# tracker.net
KiCad netlist of a schematic drawn in EAGLE
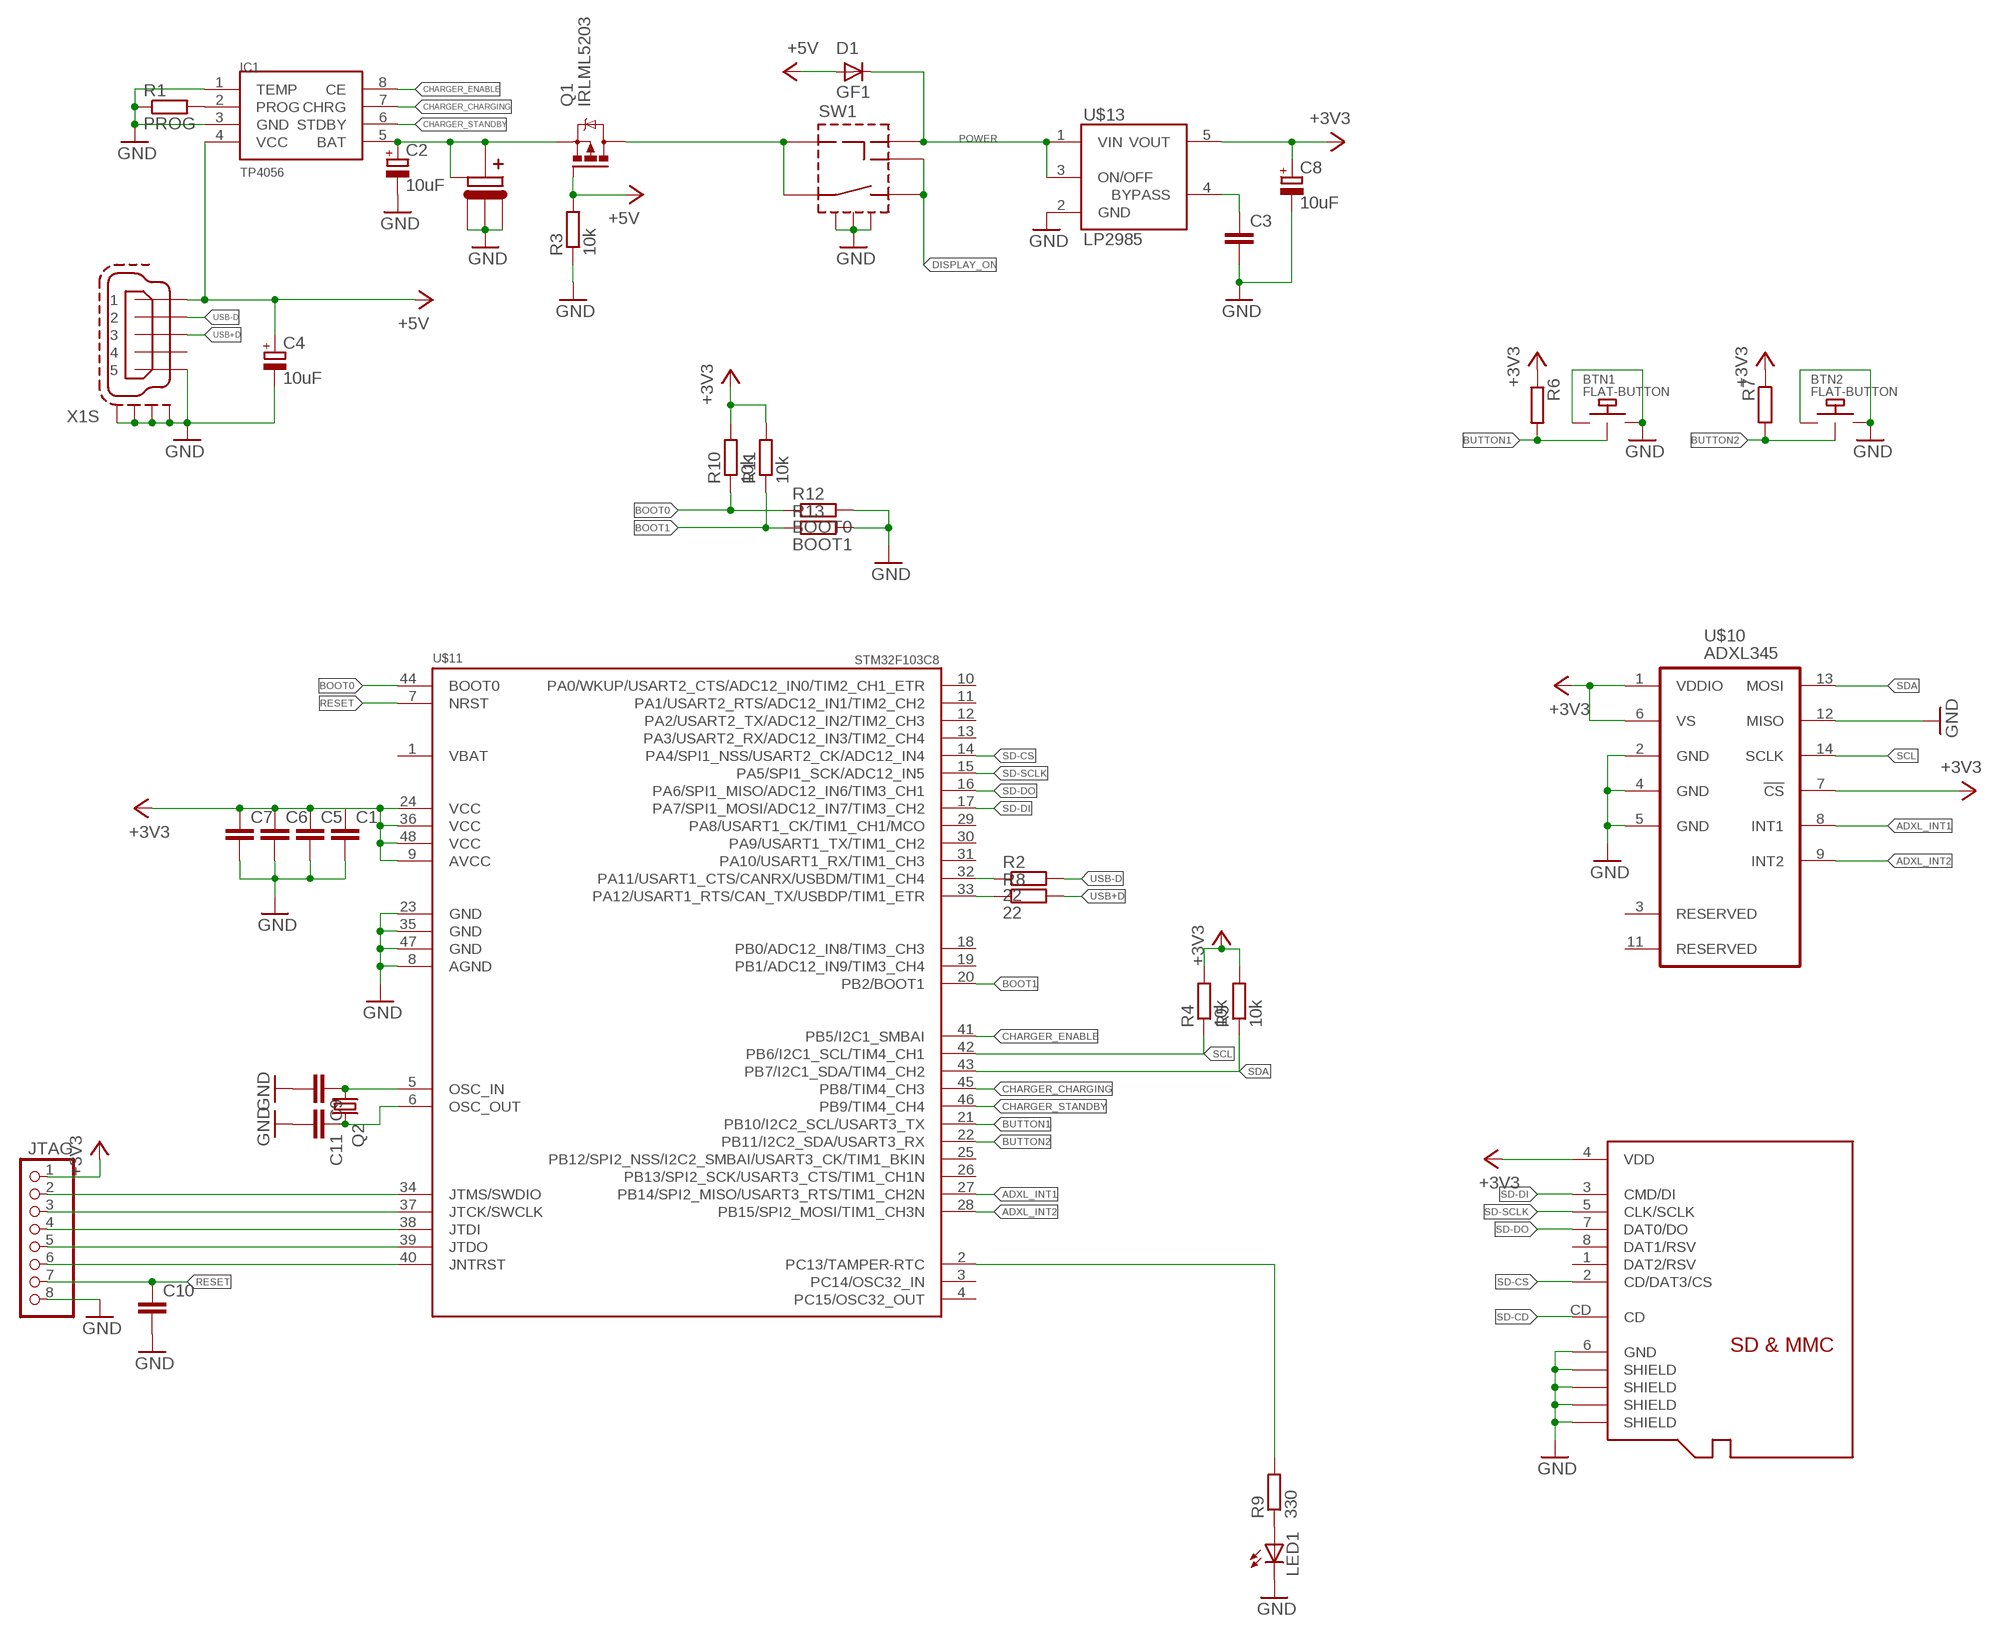
[diagram p0: schematic, sheet 1]

(export (version "E")
  (design (tool "Eeschema 10.0.6"))
  (components
    (comp (ref "BTN1")
      (value "FLAT-BUTTON")
      (footprint "eagle-import:FLAT-BUTTON")
      (libsource (lib "eagle-import") (part "FLAT-BUTTON"))
    )
    (comp (ref "BTN2")
      (value "FLAT-BUTTON")
      (footprint "eagle-import:FLAT-BUTTON")
      (libsource (lib "eagle-import") (part "FLAT-BUTTON"))
    )
    (comp (ref "C1")
      (value "C-EUC0805K")
      (footprint "eagle-import:C0805K")
      (libsource (lib "eagle-import") (part "C-EUC0805K"))
    )
    (comp (ref "C2")
      (value "10uF")
      (footprint "eagle-import:B_3528-21W")
      (libsource (lib "eagle-import") (part "CPOL-EUB/3528-21W"))
    )
    (comp (ref "C3")
      (value "C-EUC0805K")
      (footprint "eagle-import:C0805K")
      (libsource (lib "eagle-import") (part "C-EUC0805K"))
    )
    (comp (ref "C4")
      (value "10uF")
      (footprint "eagle-import:B_3528-21W")
      (libsource (lib "eagle-import") (part "CPOL-EUB/3528-21W"))
    )
    (comp (ref "C5")
      (value "C-EUC0805K")
      (footprint "eagle-import:C0805K")
      (libsource (lib "eagle-import") (part "C-EUC0805K"))
    )
    (comp (ref "C6")
      (value "C-EUC0805K")
      (footprint "eagle-import:C0805K")
      (libsource (lib "eagle-import") (part "C-EUC0805K"))
    )
    (comp (ref "C7")
      (value "C-EUC0805K")
      (footprint "eagle-import:C0805K")
      (libsource (lib "eagle-import") (part "C-EUC0805K"))
    )
    (comp (ref "C8")
      (value "10uF")
      (footprint "eagle-import:B_3528-21W")
      (libsource (lib "eagle-import") (part "CPOL-EUB/3528-21W"))
    )
    (comp (ref "C9")
      (value "C-EUC0805K")
      (footprint "eagle-import:C0805K")
      (libsource (lib "eagle-import") (part "C-EUC0805K"))
    )
    (comp (ref "C10")
      (value "C-EUC0805K")
      (footprint "eagle-import:C0805K")
      (libsource (lib "eagle-import") (part "C-EUC0805K"))
    )
    (comp (ref "C11")
      (value "C-EUC0805K")
      (footprint "eagle-import:C0805K")
      (libsource (lib "eagle-import") (part "C-EUC0805K"))
    )
    (comp (ref "D1")
      (value "GF1")
      (footprint "eagle-import:SMA-DO214AC")
      (libsource (lib "eagle-import") (part "GF1"))
    )
    (comp (ref "IC1")
      (value "TP4056")
      (footprint "eagle-import:SOP-8")
      (libsource (lib "eagle-import") (part "TP4056"))
    )
    (comp (ref "JTAG")
      (value "PINHD-1X8")
      (footprint "eagle-import:PLL1.27-1X8")
      (libsource (lib "eagle-import") (part "PINHD-1X8"))
    )
    (comp (ref "LED1")
      (value "LEDSML1206")
      (footprint "eagle-import:SML1206")
      (libsource (lib "eagle-import") (part "LEDSML1206"))
    )
    (comp (ref "Q1")
      (value "IRLML5203")
      (footprint "eagle-import:MICRO3")
      (libsource (lib "eagle-import") (part "IRLML5203"))
    )
    (comp (ref "Q2")
      (value "CRYSTALHC49S")
      (footprint "eagle-import:HC49_S")
      (libsource (lib "eagle-import") (part "CRYSTALHC49S"))
    )
    (comp (ref "R1")
      (value "PROG")
      (footprint "eagle-import:M0805")
      (libsource (lib "eagle-import") (part "R-EU_M0805"))
    )
    (comp (ref "R2")
      (value "22")
      (footprint "eagle-import:R0805")
      (libsource (lib "eagle-import") (part "R-EU_R0805"))
    )
    (comp (ref "R3")
      (value "10k")
      (footprint "eagle-import:R0805")
      (libsource (lib "eagle-import") (part "R-EU_R0805"))
    )
    (comp (ref "R4")
      (value "10k")
      (footprint "eagle-import:R0805")
      (libsource (lib "eagle-import") (part "R-EU_R0805"))
    )
    (comp (ref "R5")
      (value "10k")
      (footprint "eagle-import:R0805")
      (libsource (lib "eagle-import") (part "R-EU_R0805"))
    )
    (comp (ref "R6")
      (value "R-EU_R0805")
      (footprint "eagle-import:R0805")
      (libsource (lib "eagle-import") (part "R-EU_R0805"))
    )
    (comp (ref "R7")
      (value "R-EU_R0805")
      (footprint "eagle-import:R0805")
      (libsource (lib "eagle-import") (part "R-EU_R0805"))
    )
    (comp (ref "R8")
      (value "22")
      (footprint "eagle-import:R0805")
      (libsource (lib "eagle-import") (part "R-EU_R0805"))
    )
    (comp (ref "R9")
      (value "330")
      (footprint "eagle-import:R0805")
      (libsource (lib "eagle-import") (part "R-EU_R0805"))
    )
    (comp (ref "R10")
      (value "10k")
      (footprint "eagle-import:R0805")
      (libsource (lib "eagle-import") (part "R-EU_R0805"))
    )
    (comp (ref "R11")
      (value "10k")
      (footprint "eagle-import:R0805")
      (libsource (lib "eagle-import") (part "R-EU_R0805"))
    )
    (comp (ref "R12")
      (value "BOOT0")
      (footprint "eagle-import:R0805")
      (libsource (lib "eagle-import") (part "R-EU_R0805"))
    )
    (comp (ref "R13")
      (value "BOOT1")
      (footprint "eagle-import:R0805")
      (libsource (lib "eagle-import") (part "R-EU_R0805"))
    )
    (comp (ref "SW1")
      (value "PWR-SWITCH")
      (footprint "eagle-import:PWR-SWITCH")
      (libsource (lib "eagle-import") (part "PWR-SWITCH"))
    )
    (comp (ref "U$6")
      (value "BATTERY+")
      (footprint "eagle-import:BATTERY+")
      (libsource (lib "eagle-import") (part "BATTERY+"))
    )
    (comp (ref "U$7")
      (value "BATTERY-")
      (footprint "eagle-import:BATTERY-")
      (libsource (lib "eagle-import") (part "BATTERY-"))
    )
    (comp (ref "U$10")
      (value "ADXL345")
      (footprint "eagle-import:LGA14")
      (libsource (lib "eagle-import") (part "ADXL345"))
    )
    (comp (ref "U$11")
      (value "STM32F103C8")
      (footprint "eagle-import:LQFP48-7X7")
      (libsource (lib "eagle-import") (part "STM32F103C8"))
    )
    (comp (ref "U$12")
      (value "MICROSD")
      (footprint "eagle-import:C12075")
      (libsource (lib "eagle-import") (part "MICROSD"))
    )
    (comp (ref "U$13")
      (value "LP2985AIM5-3.3")
      (footprint "eagle-import:SOT25")
      (libsource (lib "eagle-import") (part "LP2985AIM5-3.3"))
    )
    (comp (ref "X1")
      (value "MINI-USB-SCHIELD-32005-301")
      (footprint "eagle-import:32005-301")
      (libsource (lib "eagle-import") (part "MINI-USB-SCHIELD-32005-301"))
    )
  )
  (nets
    (net (code "1") (name "+3V3") (class "Default")
      (node (ref "C1") (pin "1") (pinfunction "1_1") (pintype "passive"))
      (node (ref "C5") (pin "1") (pinfunction "1_1") (pintype "passive"))
      (node (ref "C6") (pin "1") (pinfunction "1_1") (pintype "passive"))
      (node (ref "C7") (pin "1") (pinfunction "1_1") (pintype "passive"))
      (node (ref "C8") (pin "+") (pinfunction "+_+") (pintype "passive"))
      (node (ref "JTAG") (pin "1") (pinfunction "1_1") (pintype "passive"))
      (node (ref "R10") (pin "2") (pinfunction "2_2") (pintype "passive"))
      (node (ref "R11") (pin "2") (pinfunction "2_2") (pintype "passive"))
      (node (ref "R4") (pin "2") (pinfunction "2_2") (pintype "passive"))
      (node (ref "R5") (pin "2") (pinfunction "2_2") (pintype "passive"))
      (node (ref "R6") (pin "1") (pinfunction "1_1") (pintype "passive"))
      (node (ref "R7") (pin "1") (pinfunction "1_1") (pintype "passive"))
      (node (ref "U$10") (pin "1") (pinfunction "VDDIO_1") (pintype "power_in"))
      (node (ref "U$10") (pin "6") (pinfunction "VS_6") (pintype "power_in"))
      (node (ref "U$10") (pin "7") (pinfunction "~{CS}_7") (pintype "input"))
      (node (ref "U$11") (pin "24") (pinfunction "VCC_24") (pintype "power_in"))
      (node (ref "U$11") (pin "36") (pinfunction "VCC_36") (pintype "power_in"))
      (node (ref "U$11") (pin "48") (pinfunction "VCC_48") (pintype "power_in"))
      (node (ref "U$11") (pin "9") (pinfunction "AVCC_9") (pintype "power_in"))
      (node (ref "U$12") (pin "4") (pinfunction "VDD_4") (pintype "power_in"))
      (node (ref "U$13") (pin "5") (pinfunction "VOUT_5") (pintype "power_in"))
    )
    (net (code "2") (name "+5V") (class "Default")
      (node (ref "C4") (pin "+") (pinfunction "+_+") (pintype "passive"))
      (node (ref "D1") (pin "A") (pinfunction "A_A") (pintype "passive"))
      (node (ref "IC1") (pin "4") (pinfunction "VCC_4") (pintype "bidirectional"))
      (node (ref "Q1") (pin "1") (pinfunction "G_1") (pintype "passive"))
      (node (ref "R3") (pin "2") (pinfunction "2_2") (pintype "passive"))
      (node (ref "X1") (pin "1") (pinfunction "1_1") (pintype "passive"))
    )
    (net (code "3") (name "/POWER") (class "Default")
      (node (ref "D1") (pin "K") (pinfunction "C_K") (pintype "passive"))
      (node (ref "SW1") (pin "3") (pinfunction "PWR-OUT1_3") (pintype "bidirectional"))
      (node (ref "U$13") (pin "1") (pinfunction "VIN_1") (pintype "power_in"))
      (node (ref "U$13") (pin "3") (pinfunction "ON/OFF_3") (pintype "input"))
    )
    (net (code "4") (name "/VBAT") (class "Default")
      (node (ref "U$11") (pin "1") (pinfunction "VBAT_1") (pintype "power_in"))
    )
    (net (code "5") (name "ADXL_INT1") (class "Default")
      (node (ref "U$10") (pin "8") (pinfunction "INT1_8") (pintype "output"))
      (node (ref "U$11") (pin "27") (pinfunction "PB14/SPI2_MISO/USART3_RTS/TIM1_CH2N_27") (pintype "bidirectional"))
    )
    (net (code "6") (name "ADXL_INT2") (class "Default")
      (node (ref "U$10") (pin "9") (pinfunction "INT2_9") (pintype "output"))
      (node (ref "U$11") (pin "28") (pinfunction "PB15/SPI2_MOSI/TIM1_CH3N_28") (pintype "bidirectional"))
    )
    (net (code "7") (name "BOOT0") (class "Default")
      (node (ref "R10") (pin "1") (pinfunction "1_1") (pintype "passive"))
      (node (ref "R12") (pin "1") (pinfunction "1_1") (pintype "passive"))
      (node (ref "U$11") (pin "44") (pinfunction "BOOT0_44") (pintype "bidirectional"))
    )
    (net (code "8") (name "BOOT1") (class "Default")
      (node (ref "R11") (pin "1") (pinfunction "1_1") (pintype "passive"))
      (node (ref "R13") (pin "1") (pinfunction "1_1") (pintype "passive"))
      (node (ref "U$11") (pin "20") (pinfunction "PB2/BOOT1_20") (pintype "bidirectional"))
    )
    (net (code "9") (name "BUTTON1") (class "Default")
      (node (ref "BTN1") (pin "1") (pinfunction "2_1") (pintype "bidirectional"))
      (node (ref "R6") (pin "2") (pinfunction "2_2") (pintype "passive"))
      (node (ref "U$11") (pin "21") (pinfunction "PB10/I2C2_SCL/USART3_TX_21") (pintype "bidirectional"))
    )
    (net (code "10") (name "BUTTON2") (class "Default")
      (node (ref "BTN2") (pin "1") (pinfunction "2_1") (pintype "bidirectional"))
      (node (ref "R7") (pin "2") (pinfunction "2_2") (pintype "passive"))
      (node (ref "U$11") (pin "22") (pinfunction "PB11/I2C2_SDA/USART3_RX_22") (pintype "bidirectional"))
    )
    (net (code "11") (name "CHARGER_CHARGING") (class "Default")
      (node (ref "IC1") (pin "7") (pinfunction "CHRG_7") (pintype "bidirectional"))
      (node (ref "U$11") (pin "45") (pinfunction "PB8/TIM4_CH3_45") (pintype "bidirectional"))
    )
    (net (code "12") (name "CHARGER_ENABLE") (class "Default")
      (node (ref "IC1") (pin "8") (pinfunction "CE_8") (pintype "bidirectional"))
      (node (ref "U$11") (pin "41") (pinfunction "PB5/I2C1_SMBAI_41") (pintype "bidirectional"))
    )
    (net (code "13") (name "CHARGER_STANDBY") (class "Default")
      (node (ref "IC1") (pin "6") (pinfunction "STDBY_6") (pintype "bidirectional"))
      (node (ref "U$11") (pin "46") (pinfunction "PB9/TIM4_CH4_46") (pintype "bidirectional"))
    )
    (net (code "14") (name "DISPLAY_ON") (class "Default")
      (node (ref "SW1") (pin "4") (pinfunction "BTN2_4") (pintype "bidirectional"))
      (node (ref "SW1") (pin "5") (pinfunction "PWR-OUT2_5") (pintype "bidirectional"))
    )
    (net (code "15") (name "GND") (class "Default")
      (node (ref "BTN1") (pin "2") (pinfunction "1_2") (pintype "bidirectional"))
      (node (ref "BTN1") (pin "3") (pinfunction "1_3") (pintype "bidirectional"))
      (node (ref "BTN2") (pin "2") (pinfunction "1_2") (pintype "bidirectional"))
      (node (ref "BTN2") (pin "3") (pinfunction "1_3") (pintype "bidirectional"))
      (node (ref "C1") (pin "2") (pinfunction "2_2") (pintype "passive"))
      (node (ref "C10") (pin "2") (pinfunction "2_2") (pintype "passive"))
      (node (ref "C11") (pin "2") (pinfunction "2_2") (pintype "passive"))
      (node (ref "C2") (pin "-") (pinfunction "-_-") (pintype "passive"))
      (node (ref "C3") (pin "2") (pinfunction "2_2") (pintype "passive"))
      (node (ref "C4") (pin "-") (pinfunction "-_-") (pintype "passive"))
      (node (ref "C5") (pin "2") (pinfunction "2_2") (pintype "passive"))
      (node (ref "C6") (pin "2") (pinfunction "2_2") (pintype "passive"))
      (node (ref "C7") (pin "2") (pinfunction "2_2") (pintype "passive"))
      (node (ref "C8") (pin "-") (pinfunction "-_-") (pintype "passive"))
      (node (ref "C9") (pin "2") (pinfunction "2_2") (pintype "passive"))
      (node (ref "IC1") (pin "1") (pinfunction "TEMP_1") (pintype "bidirectional"))
      (node (ref "IC1") (pin "3") (pinfunction "GND_3") (pintype "bidirectional"))
      (node (ref "JTAG") (pin "8") (pinfunction "8_8") (pintype "passive"))
      (node (ref "LED1") (pin "C") (pinfunction "C_C") (pintype "passive"))
      (node (ref "R1") (pin "1") (pinfunction "1_1") (pintype "passive"))
      (node (ref "R12") (pin "2") (pinfunction "2_2") (pintype "passive"))
      (node (ref "R13") (pin "2") (pinfunction "2_2") (pintype "passive"))
      (node (ref "R3") (pin "1") (pinfunction "1_1") (pintype "passive"))
      (node (ref "SW1") (pin "SCREEN@1") (pinfunction "SHIELD_SCREEN@1") (pintype "power_in"))
      (node (ref "SW1") (pin "SCREEN@2") (pinfunction "SHIELD_SCREEN@2") (pintype "power_in"))
      (node (ref "SW1") (pin "SCREEN@3") (pinfunction "SHIELD_SCREEN@3") (pintype "power_in"))
      (node (ref "U$10") (pin "12") (pinfunction "MISO_12") (pintype "output"))
      (node (ref "U$10") (pin "2") (pinfunction "GND_2") (pintype "power_in"))
      (node (ref "U$10") (pin "4") (pinfunction "GND_4") (pintype "power_in"))
      (node (ref "U$10") (pin "5") (pinfunction "GND_5") (pintype "power_in"))
      (node (ref "U$11") (pin "23") (pinfunction "GND_23") (pintype "power_in"))
      (node (ref "U$11") (pin "35") (pinfunction "GND_35") (pintype "power_in"))
      (node (ref "U$11") (pin "47") (pinfunction "GND_47") (pintype "power_in"))
      (node (ref "U$11") (pin "8") (pinfunction "AGND_8") (pintype "power_in"))
      (node (ref "U$12") (pin "6") (pinfunction "GND_6") (pintype "power_in"))
      (node (ref "U$12") (pin "GND@1") (pinfunction "SHIELD_GND@1") (pintype "power_in"))
      (node (ref "U$12") (pin "GND@2") (pinfunction "SHIELD_GND@2") (pintype "power_in"))
      (node (ref "U$12") (pin "GND@3") (pinfunction "SHIELD_GND@3") (pintype "power_in"))
      (node (ref "U$12") (pin "GND@4") (pinfunction "SHIELD_GND@4") (pintype "power_in"))
      (node (ref "U$13") (pin "2") (pinfunction "GND_2") (pintype "power_in"))
      (node (ref "U$7") (pin "P$1") (pinfunction "BATTERY-_P$1") (pintype "power_in"))
      (node (ref "U$7") (pin "P$2") (pinfunction "BATTERY-_P$2") (pintype "power_in"))
      (node (ref "U$7") (pin "P$3") (pinfunction "BATTERY-_P$3") (pintype "power_in"))
      (node (ref "X1") (pin "5") (pinfunction "5_5") (pintype "passive"))
      (node (ref "X1") (pin "M1") (pinfunction "S1_M1") (pintype "passive"))
      (node (ref "X1") (pin "M2") (pinfunction "S2_M2") (pintype "passive"))
      (node (ref "X1") (pin "M3") (pinfunction "S3_M3") (pintype "passive"))
      (node (ref "X1") (pin "M4") (pinfunction "S4_M4") (pintype "passive"))
    )
    (net (code "16") (name "Net-(IC1-BAT)") (class "Default")
      (node (ref "C2") (pin "+") (pinfunction "+_+") (pintype "passive"))
      (node (ref "IC1") (pin "5") (pinfunction "BAT_5") (pintype "bidirectional"))
      (node (ref "Q1") (pin "2") (pinfunction "S_2") (pintype "passive"))
      (node (ref "U$6") (pin "PAD") (pinfunction "BATTERY+#1_PAD") (pintype "power_in"))
      (node (ref "U$6") (pin "PIN") (pinfunction "BATTERY+#2_PIN") (pintype "power_in"))
    )
    (net (code "17") (name "Net-(IC1-PROG)") (class "Default")
      (node (ref "IC1") (pin "2") (pinfunction "PROG_2") (pintype "bidirectional"))
      (node (ref "R1") (pin "2") (pinfunction "2_2") (pintype "passive"))
    )
    (net (code "18") (name "Net-(LED1-PadA)") (class "Default")
      (node (ref "LED1") (pin "A") (pinfunction "A_A") (pintype "passive"))
      (node (ref "R9") (pin "1") (pinfunction "1_1") (pintype "passive"))
    )
    (net (code "19") (name "Net-(Q1-D)") (class "Default")
      (node (ref "Q1") (pin "3") (pinfunction "D_3") (pintype "passive"))
      (node (ref "SW1") (pin "1") (pinfunction "BTN1_1") (pintype "bidirectional"))
      (node (ref "SW1") (pin "2") (pinfunction "PWR-IN_2") (pintype "bidirectional"))
    )
    (net (code "20") (name "Net-(U$11-JNTRST)") (class "Default")
      (node (ref "JTAG") (pin "6") (pinfunction "6_6") (pintype "passive"))
      (node (ref "U$11") (pin "40") (pinfunction "JNTRST_40") (pintype "bidirectional"))
    )
    (net (code "21") (name "Net-(U$11-JTCK{slash}SWCLK)") (class "Default")
      (node (ref "JTAG") (pin "3") (pinfunction "3_3") (pintype "passive"))
      (node (ref "U$11") (pin "37") (pinfunction "JTCK/SWCLK_37") (pintype "bidirectional"))
    )
    (net (code "22") (name "Net-(U$11-JTDI)") (class "Default")
      (node (ref "JTAG") (pin "4") (pinfunction "4_4") (pintype "passive"))
      (node (ref "U$11") (pin "38") (pinfunction "JTDI_38") (pintype "bidirectional"))
    )
    (net (code "23") (name "Net-(U$11-JTDO)") (class "Default")
      (node (ref "JTAG") (pin "5") (pinfunction "5_5") (pintype "passive"))
      (node (ref "U$11") (pin "39") (pinfunction "JTDO_39") (pintype "bidirectional"))
    )
    (net (code "24") (name "Net-(U$11-JTMS{slash}SWDIO)") (class "Default")
      (node (ref "JTAG") (pin "2") (pinfunction "2_2") (pintype "passive"))
      (node (ref "U$11") (pin "34") (pinfunction "JTMS/SWDIO_34") (pintype "bidirectional"))
    )
    (net (code "25") (name "Net-(U$11-OSC_IN)") (class "Default")
      (node (ref "C9") (pin "1") (pinfunction "1_1") (pintype "passive"))
      (node (ref "Q2") (pin "1") (pinfunction "1_1") (pintype "passive"))
      (node (ref "U$11") (pin "5") (pinfunction "OSC_IN_5") (pintype "input"))
    )
    (net (code "26") (name "Net-(U$11-OSC_OUT)") (class "Default")
      (node (ref "C11") (pin "1") (pinfunction "1_1") (pintype "passive"))
      (node (ref "Q2") (pin "2") (pinfunction "2_2") (pintype "passive"))
      (node (ref "U$11") (pin "6") (pinfunction "OSC_OUT_6") (pintype "output"))
    )
    (net (code "27") (name "Net-(U$11-PA11{slash}USART1_CTS{slash}CANRX{slash}USBDM{slash}TIM1_CH4)") (class "Default")
      (node (ref "R2") (pin "1") (pinfunction "1_1") (pintype "passive"))
      (node (ref "U$11") (pin "32") (pinfunction "PA11/USART1_CTS/CANRX/USBDM/TIM1_CH4_32") (pintype "bidirectional"))
    )
    (net (code "28") (name "Net-(U$11-PA12{slash}USART1_RTS{slash}CAN_TX{slash}USBDP{slash}TIM1_ETR)") (class "Default")
      (node (ref "R8") (pin "1") (pinfunction "1_1") (pintype "passive"))
      (node (ref "U$11") (pin "33") (pinfunction "PA12/USART1_RTS/CAN_TX/USBDP/TIM1_ETR_33") (pintype "bidirectional"))
    )
    (net (code "29") (name "Net-(U$11-PC13{slash}TAMPER-RTC)") (class "Default")
      (node (ref "R9") (pin "2") (pinfunction "2_2") (pintype "passive"))
      (node (ref "U$11") (pin "2") (pinfunction "PC13/TAMPER-RTC_2") (pintype "bidirectional"))
    )
    (net (code "30") (name "Net-(U$13-BYPASS)") (class "Default")
      (node (ref "C3") (pin "1") (pinfunction "1_1") (pintype "passive"))
      (node (ref "U$13") (pin "4") (pinfunction "BYPASS_4") (pintype "power_in"))
    )
    (net (code "31") (name "RESET") (class "Default")
      (node (ref "C10") (pin "1") (pinfunction "1_1") (pintype "passive"))
      (node (ref "JTAG") (pin "7") (pinfunction "7_7") (pintype "passive"))
      (node (ref "U$11") (pin "7") (pinfunction "NRST_7") (pintype "bidirectional"))
    )
    (net (code "32") (name "SCL") (class "Default")
      (node (ref "R4") (pin "1") (pinfunction "1_1") (pintype "passive"))
      (node (ref "U$10") (pin "14") (pinfunction "SCLK_14") (pintype "input"))
      (node (ref "U$11") (pin "42") (pinfunction "PB6/I2C1_SCL/TIM4_CH1_42") (pintype "bidirectional"))
    )
    (net (code "33") (name "SD-CD") (class "Default")
      (node (ref "U$12") (pin "CD") (pinfunction "CD_CD") (pintype "bidirectional"))
    )
    (net (code "34") (name "SD-CS") (class "Default")
      (node (ref "U$11") (pin "14") (pinfunction "PA4/SPI1_NSS/USART2_CK/ADC12_IN4_14") (pintype "bidirectional"))
      (node (ref "U$12") (pin "2") (pinfunction "CD/DAT3/CS_2") (pintype "bidirectional"))
    )
    (net (code "35") (name "SD-DI") (class "Default")
      (node (ref "U$11") (pin "17") (pinfunction "PA7/SPI1_MOSI/ADC12_IN7/TIM3_CH2_17") (pintype "bidirectional"))
      (node (ref "U$12") (pin "3") (pinfunction "CMD/DI_3") (pintype "bidirectional"))
    )
    (net (code "36") (name "SD-DO") (class "Default")
      (node (ref "U$11") (pin "16") (pinfunction "PA6/SPI1_MISO/ADC12_IN6/TIM3_CH1_16") (pintype "bidirectional"))
      (node (ref "U$12") (pin "7") (pinfunction "DAT0/DO_7") (pintype "bidirectional"))
    )
    (net (code "37") (name "SD-SCLK") (class "Default")
      (node (ref "U$11") (pin "15") (pinfunction "PA5/SPI1_SCK/ADC12_IN5_15") (pintype "bidirectional"))
      (node (ref "U$12") (pin "5") (pinfunction "CLK/SCLK_5") (pintype "bidirectional"))
    )
    (net (code "38") (name "SDA") (class "Default")
      (node (ref "R5") (pin "1") (pinfunction "1_1") (pintype "passive"))
      (node (ref "U$10") (pin "13") (pinfunction "MOSI_13") (pintype "input"))
      (node (ref "U$11") (pin "43") (pinfunction "PB7/I2C1_SDA/TIM4_CH2_43") (pintype "bidirectional"))
    )
    (net (code "39") (name "USB+D") (class "Default")
      (node (ref "R8") (pin "2") (pinfunction "2_2") (pintype "passive"))
      (node (ref "X1") (pin "3") (pinfunction "3_3") (pintype "passive"))
    )
    (net (code "40") (name "USB-D") (class "Default")
      (node (ref "R2") (pin "2") (pinfunction "2_2") (pintype "passive"))
      (node (ref "X1") (pin "2") (pinfunction "2_2") (pintype "passive"))
    )
    (net (code "41") (name "unconnected-(U$10-NC-Pad10)") (class "Default")
      (node (ref "U$10") (pin "10") (pinfunction "NC_10") (pintype "no_connect"))
    )
    (net (code "42") (name "unconnected-(U$10-RESERVED-Pad3)") (class "Default")
      (node (ref "U$10") (pin "3") (pinfunction "RESERVED_3") (pintype "bidirectional"))
    )
    (net (code "43") (name "unconnected-(U$10-RESERVED-Pad11)") (class "Default")
      (node (ref "U$10") (pin "11") (pinfunction "RESERVED_11") (pintype "bidirectional"))
    )
    (net (code "44") (name "unconnected-(U$11-PA0{slash}WKUP{slash}USART2_CTS{slash}ADC12_IN0{slash}TIM2_CH1_ETR-Pad10)") (class "Default")
      (node (ref "U$11") (pin "10") (pinfunction "PA0/WKUP/USART2_CTS/ADC12_IN0/TIM2_CH1_ETR_10") (pintype "bidirectional"))
    )
    (net (code "45") (name "unconnected-(U$11-PA1{slash}USART2_RTS{slash}ADC12_IN1{slash}TIM2_CH2-Pad11)") (class "Default")
      (node (ref "U$11") (pin "11") (pinfunction "PA1/USART2_RTS/ADC12_IN1/TIM2_CH2_11") (pintype "bidirectional"))
    )
    (net (code "46") (name "unconnected-(U$11-PA2{slash}USART2_TX{slash}ADC12_IN2{slash}TIM2_CH3-Pad12)") (class "Default")
      (node (ref "U$11") (pin "12") (pinfunction "PA2/USART2_TX/ADC12_IN2/TIM2_CH3_12") (pintype "bidirectional"))
    )
    (net (code "47") (name "unconnected-(U$11-PA3{slash}USART2_RX{slash}ADC12_IN3{slash}TIM2_CH4-Pad13)") (class "Default")
      (node (ref "U$11") (pin "13") (pinfunction "PA3/USART2_RX/ADC12_IN3/TIM2_CH4_13") (pintype "bidirectional"))
    )
    (net (code "48") (name "unconnected-(U$11-PA8{slash}USART1_CK{slash}TIM1_CH1{slash}MCO-Pad29)") (class "Default")
      (node (ref "U$11") (pin "29") (pinfunction "PA8/USART1_CK/TIM1_CH1/MCO_29") (pintype "bidirectional"))
    )
    (net (code "49") (name "unconnected-(U$11-PA9{slash}USART1_TX{slash}TIM1_CH2-Pad30)") (class "Default")
      (node (ref "U$11") (pin "30") (pinfunction "PA9/USART1_TX/TIM1_CH2_30") (pintype "bidirectional"))
    )
    (net (code "50") (name "unconnected-(U$11-PA10{slash}USART1_RX{slash}TIM1_CH3-Pad31)") (class "Default")
      (node (ref "U$11") (pin "31") (pinfunction "PA10/USART1_RX/TIM1_CH3_31") (pintype "bidirectional"))
    )
    (net (code "51") (name "unconnected-(U$11-PB0{slash}ADC12_IN8{slash}TIM3_CH3-Pad18)") (class "Default")
      (node (ref "U$11") (pin "18") (pinfunction "PB0/ADC12_IN8/TIM3_CH3_18") (pintype "bidirectional"))
    )
    (net (code "52") (name "unconnected-(U$11-PB1{slash}ADC12_IN9{slash}TIM3_CH4-Pad19)") (class "Default")
      (node (ref "U$11") (pin "19") (pinfunction "PB1/ADC12_IN9/TIM3_CH4_19") (pintype "bidirectional"))
    )
    (net (code "53") (name "unconnected-(U$11-PB12{slash}SPI2_NSS{slash}I2C2_SMBAI{slash}USART3_CK{slash}TIM1_BKIN-Pad25)") (class "Default")
      (node (ref "U$11") (pin "25") (pinfunction "PB12/SPI2_NSS/I2C2_SMBAI/USART3_CK/TIM1_BKIN_25") (pintype "bidirectional"))
    )
    (net (code "54") (name "unconnected-(U$11-PB13{slash}SPI2_SCK{slash}USART3_CTS{slash}TIM1_CH1N-Pad26)") (class "Default")
      (node (ref "U$11") (pin "26") (pinfunction "PB13/SPI2_SCK/USART3_CTS/TIM1_CH1N_26") (pintype "bidirectional"))
    )
    (net (code "55") (name "unconnected-(U$11-PC14{slash}OSC32_IN-Pad3)") (class "Default")
      (node (ref "U$11") (pin "3") (pinfunction "PC14/OSC32_IN_3") (pintype "bidirectional"))
    )
    (net (code "56") (name "unconnected-(U$11-PC15{slash}OSC32_OUT-Pad4)") (class "Default")
      (node (ref "U$11") (pin "4") (pinfunction "PC15/OSC32_OUT_4") (pintype "bidirectional"))
    )
    (net (code "57") (name "unconnected-(U$12-DAT1{slash}RSV-Pad8)") (class "Default")
      (node (ref "U$12") (pin "8") (pinfunction "DAT1/RSV_8") (pintype "bidirectional"))
    )
    (net (code "58") (name "unconnected-(U$12-DAT2{slash}RSV-Pad1)") (class "Default")
      (node (ref "U$12") (pin "1") (pinfunction "DAT2/RSV_1") (pintype "bidirectional"))
    )
    (net (code "59") (name "unconnected-(X1-Pad4)") (class "Default")
      (node (ref "X1") (pin "4") (pinfunction "4_4") (pintype "passive"))
    )
  )
)
